# Main.net
KiCad netlist of a schematic drawn in Altium Designer
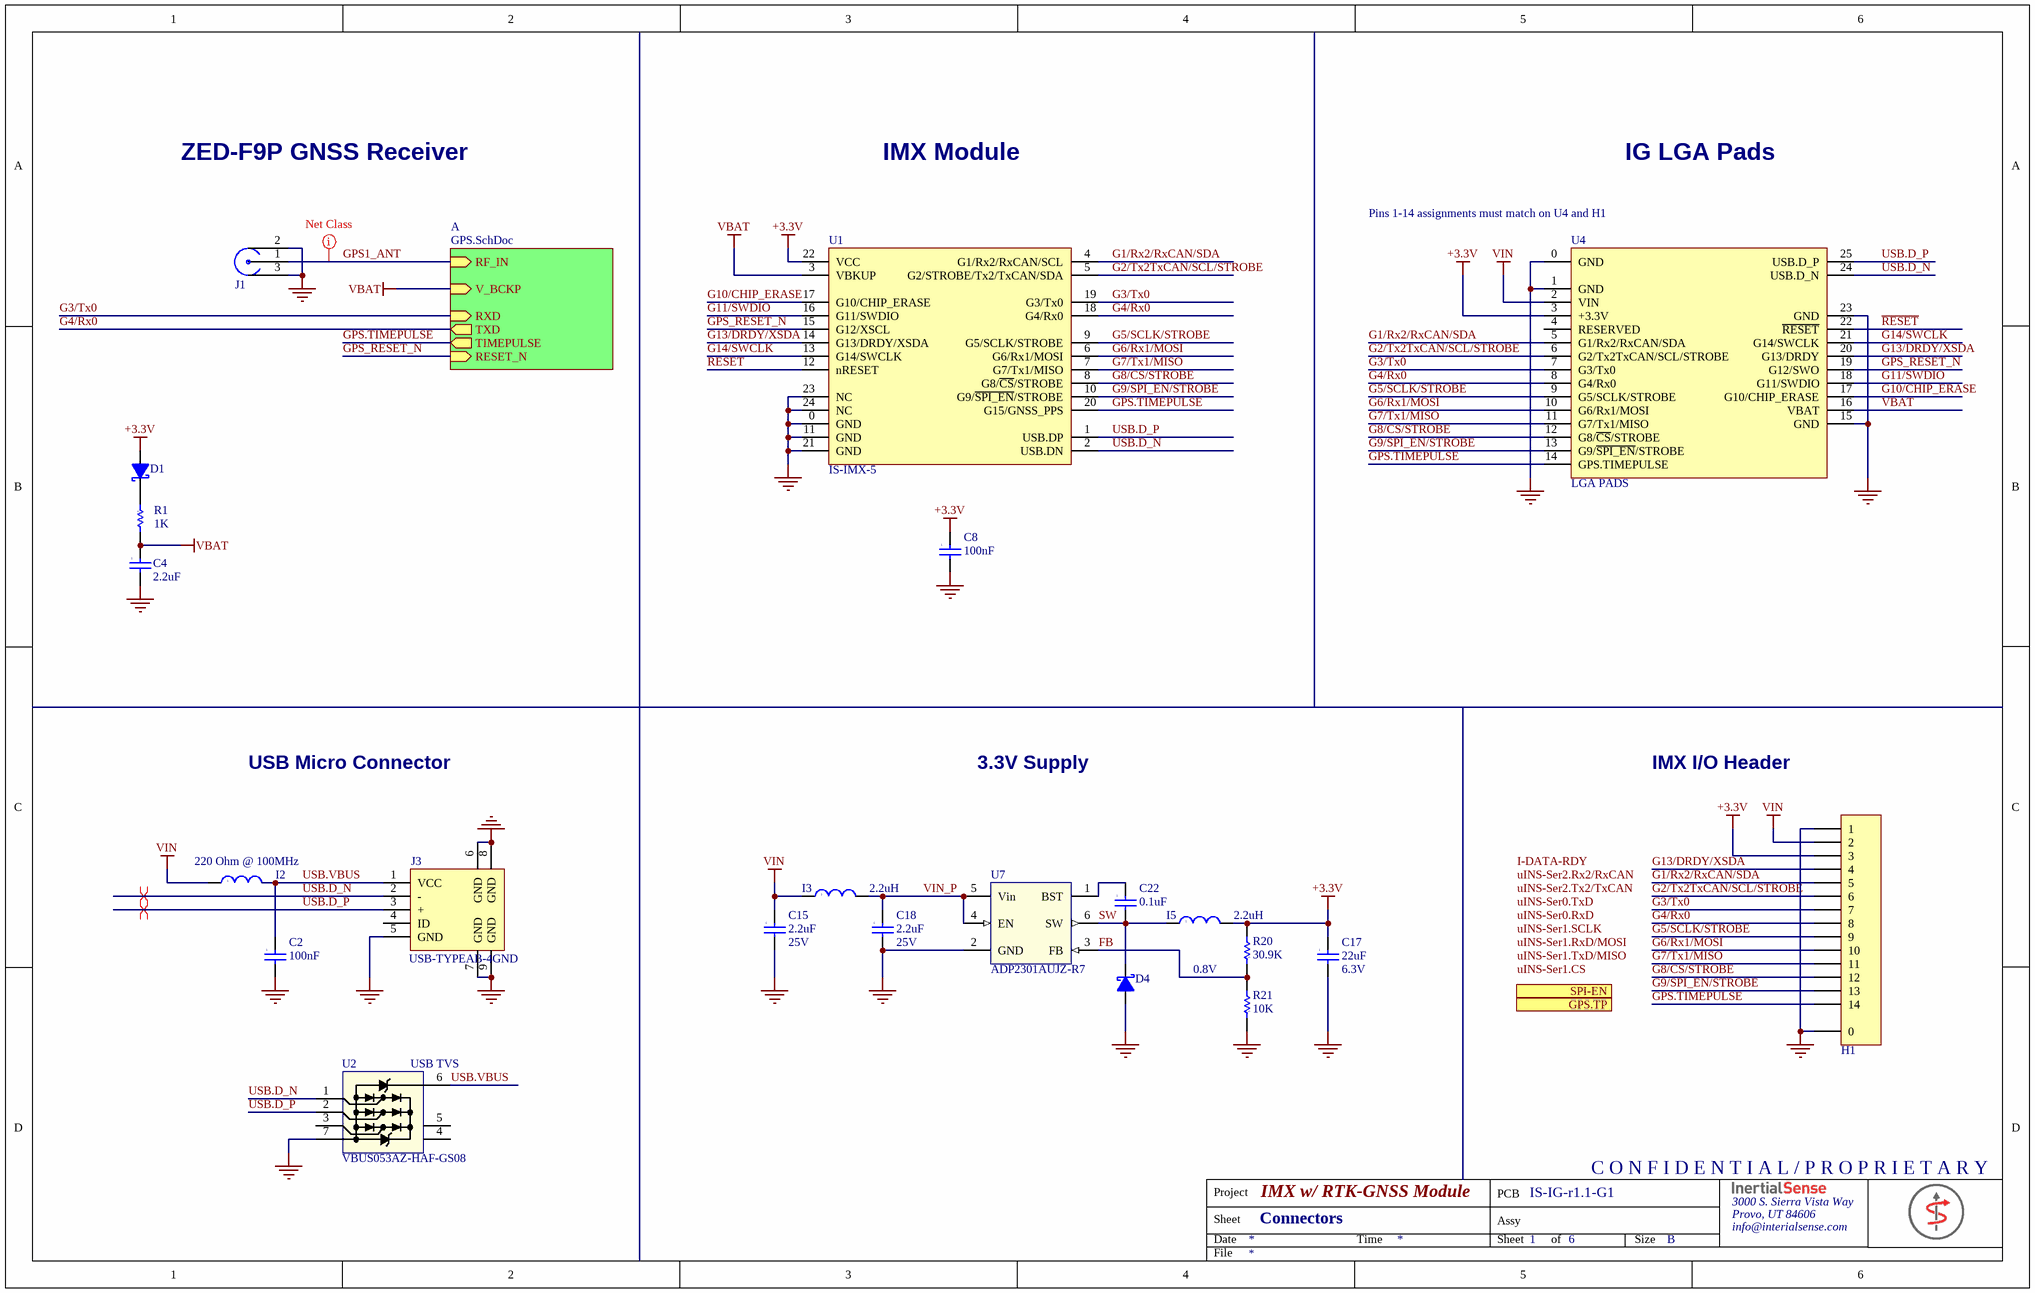
[diagram p0: Main.SchDoc]

(export (version "E")
  (design (tool "Eeschema 10.0.6"))
  (components
    (comp (ref "C2")
      (value "100nF")
      (footprint "0402")
      (description "CAP CER .10UF 50V X7R 10% 0402")
      (fields
        (field (name "MANUFACTURER") "TDK Corporation")
        (field (name "MANUFACTURER PART NUMBER") "C1005X7R1H104K")
        (field (name "PUBLISHER") "Altium Limited")
      )
      (libsource (lib "General") (part "Cap"))
    )
    (comp (ref "C4")
      (value "2.2uF")
      (footprint "0402")
      (description "0402 2.2 uF 6.3 V ±10% Tolerance X6S Multilayer Ceramic Capacitor")
      (fields
        (field (name "MANUFACTURER") "Murata")
        (field (name "MANUFACTURER PART NUMBER") "GRM155C80J225KE95D")
        (field (name "PUBLISHER") "Altium Limited")
      )
      (libsource (lib "") (part "Cap_1"))
    )
    (comp (ref "C8")
      (value "100nF")
      (footprint "0402")
      (description "CAP CER .10UF 50V X7R 10% 0402")
      (fields
        (field (name "MANUFACTURER") "TDK Corporation")
        (field (name "MANUFACTURER PART NUMBER") "C1005X7R1H104K")
        (field (name "PUBLISHER") "Altium Limited")
      )
      (libsource (lib "General") (part "Cap"))
    )
    (comp (ref "C15")
      (value "2.2uF")
      (footprint "0603")
      (description "CAP CER 2.2UF 25V X6S 0603")
      (fields
        (field (name "MANUFACTURER") "Murata")
        (field (name "MANUFACTURER PART NUMBER") "GRT188C81E225KE13D")
        (field (name "VOLTAGE RATING") "25V")
        (field (name "PUBLISHER") "Altium Limited")
      )
      (libsource (lib "") (part "Cap_1"))
    )
    (comp (ref "C17")
      (value "22uF")
      (footprint "0603")
      (description "CAP CER 22UF 6.3V X6S 0603")
      (fields
        (field (name "MANUFACTURER") "Murata")
        (field (name "MANUFACTURER PART NUMBER") "GRM188C80J226ME15D")
        (field (name "VOLTAGE RATING") "6.3V")
        (field (name "PUBLISHER") "Altium Limited")
      )
      (libsource (lib "") (part "Cap_1"))
    )
    (comp (ref "C18")
      (value "2.2uF")
      (footprint "0603")
      (description "CAP CER 2.2UF 25V X6S 0603")
      (fields
        (field (name "MANUFACTURER") "Murata")
        (field (name "MANUFACTURER PART NUMBER") "GRT188C81E225KE13D")
        (field (name "VOLTAGE RATING") "25V")
        (field (name "PUBLISHER") "Altium Limited")
      )
      (libsource (lib "") (part "Cap_1"))
    )
    (comp (ref "C22")
      (value "0.1uF")
      (footprint "0402")
      (description "CAP CER 0.1UF 50V X7R 0402")
      (fields
        (field (name "MANUFACTURER") "TDK")
        (field (name "MANUFACTURER PART NUMBER") "CGA2B3X7R1H104K050BB")
        (field (name "PUBLISHER") "Altium Limited")
      )
      (libsource (lib "") (part "Cap_1"))
    )
    (comp (ref "D1")
      (value "Diode - Schottky")
      (footprint "D0603B")
      (description "DIODE SCHOTTKY 30V 2A 0603")
      (fields
        (field (name "MANUFACTURER") "Vishay")
        (field (name "MANUFACTURER PART NUMBER") "VSKY20301608-G4-08")
      )
      (libsource (lib "General") (part "Diode - Schottky"))
    )
    (comp (ref "D4")
      (value "Diode - Schottky")
      (footprint "D0603B")
      (description "DIODE SCHOTTKY 30V 2A 0603")
      (fields
        (field (name "MANUFACTURER") "Vishay")
        (field (name "MANUFACTURER PART NUMBER") "VSKY20301608-G4-08")
      )
      (libsource (lib "General") (part "Diode - Schottky"))
    )
    (comp (ref "H1")
      (value "Hdr - 14pin - mount")
      (footprint "SM14B-GHS-TB(LF)(SN)")
      (description "Conn Shrouded Header HDR 14 POS 1.25mm Solder ST Top Entry SMD T/R")
      (fields
        (field (name "MANUFACTURER") "JST")
        (field (name "MANUFACTURER PART NUMBER") "SM14B-GHS-TB(LF)(SN)")
      )
      (libsource (lib "Connectors") (part "Hdr - 14pin - mount"))
    )
    (comp (ref "I2")
      (value "220 Ohm @ 100MHz")
      (footprint "I0603")
      (description "FERRITE CHIP 220 OHM 2500MA 0603")
      (fields
        (field (name "MANUFACTURER") "Murata Electronics North America")
        (field (name "MANUFACTURER PART NUMBER") "BLM18SG221TN1D")
      )
      (libsource (lib "") (part "Inductor_1"))
    )
    (comp (ref "I3")
      (value "2.2uH")
      (footprint "0806")
      (description "FIXED IND 2.2UH 1.2A 110 MOHM")
      (fields
        (field (name "MANUFACTURER") "TDK")
        (field (name "MANUFACTURER PART NUMBER") "MLP2016H2R2MT0S1")
      )
      (libsource (lib "General") (part "Inductor"))
    )
    (comp (ref "I5")
      (value "2.2uH")
      (footprint "0806")
      (description "FIXED IND 2.2UH 1.2A 110 MOHM")
      (fields
        (field (name "MANUFACTURER") "TDK")
        (field (name "MANUFACTURER PART NUMBER") "MLP2016H2R2MT0S1")
      )
      (libsource (lib "General") (part "Inductor"))
    )
    (comp (ref "J1")
      (value "RF - GND x 2")
      (footprint "RF UMC SMD")
      (description "CONN UMC RCPT STR 50 OHM SMD")
      (fields
        (field (name "MANUFACTURER") "Emerson Network Power Connectivity Johnson")
        (field (name "MANUFACTURER PART NUMBER") "128-0711-201")
      )
      (libsource (lib "Connectors") (part "RF - GND x 2"))
    )
    (comp (ref "J3")
      (value "USB-TYPEAB-4GND")
      (footprint "USB Micro AB R/A THR")
      (description "CONN USB AB 4POS")
      (fields
        (field (name "MANUFACTURER") "Amphenol FCI")
        (field (name "MANUFACTURER PART NUMBER") "10118194-0001LF")
      )
      (libsource (lib "Connectors") (part "USB-TYPEAB-4GND"))
    )
    (comp (ref "R1")
      (value "1K")
      (footprint "R0402")
      (description "1 kOhms ±1% 0.063W, 1/16W Chip Resistor 0402 (1005 Metric) Moisture Resistant Thick Film")
      (fields
        (field (name "MANUFACTURER") "Yageo")
        (field (name "MANUFACTURER PART NUMBER") "RC0402FR-071KL")
      )
      (libsource (lib "") (part "Res_1"))
    )
    (comp (ref "R20")
      (value "30.9K")
      (footprint "R0402")
      (description "RES TF 30.9K OHM 1% 1/16W 0402")
      (fields
        (field (name "MANUFACTURER") "Stackpole Electronics Inc")
        (field (name "MANUFACTURER PART NUMBER") "RMCF0402FT30K9")
      )
      (libsource (lib "General") (part "Res"))
    )
    (comp (ref "R21")
      (value "10K")
      (footprint "R0402")
      (description "RES 10.0K OHM 1/16W 1% 0402 SMD")
      (fields
        (field (name "MANUFACTURER") "Yageo")
        (field (name "MANUFACTURER PART NUMBER") "RC0402FR-0710KL")
      )
      (libsource (lib "General") (part "Res"))
    )
    (comp (ref "U1")
      (value "IMX")
      (footprint "IS-IMX-5.0")
      (description "Inertial Sense IMX")
      (fields
        (field (name "MANUFACTURER") "Inertial Sense")
        (field (name "MANUFACTURER PART NUMBER") "IS-IMX-5")
      )
      (libsource (lib "IS-IMX-5") (part "IS-IMX-5.0"))
    )
    (comp (ref "U2")
      (value "VBUS053")
      (footprint "QFN50P160X160X60-6N")
      (description "ESD SUPPRESS 5.5V 36W 3-Line USB")
      (fields
        (field (name "MANUFACTURER") "Vishay Semiconductors")
        (field (name "MANUFACTURER PART NUMBER") "VBUS053AZ-HAF-GS08")
      )
      (libsource (lib "ICs") (part "VBUS053"))
    )
    (comp (ref "U4")
      (value "LGA PADS")
      (footprint "IG-1.1-G1_LGA")
      (description "IMX multi-frequency RTK-GNSS Module")
      (libsource (lib "Sensors") (part "IG_1.1_LGA"))
    )
    (comp (ref "U7")
      (value "ADP2301")
      (footprint "MO-178-AB")
      (description "IC BUCK ADJ 1.2A 6TSOT")
      (fields
        (field (name "MANUFACTURER") "Analog Devices Inc")
        (field (name "MANUFACTURER PART NUMBER") "ADP2301AUJZ-R7")
      )
      (libsource (lib "ICs") (part "ADP2301"))
    )
  )
  (nets
    (net (code "1") (name "+3.3V") (class "Default")
      (node (ref "C17") (pin "1") (pinfunction "1_1") (pintype "passive"))
      (node (ref "C8") (pin "1") (pinfunction "1_1") (pintype "passive"))
      (node (ref "D1") (pin "A") (pinfunction "A_A") (pintype "passive"))
      (node (ref "H1") (pin "3") (pinfunction "3_3") (pintype "passive"))
      (node (ref "I5") (pin "2") (pinfunction "2_2") (pintype "passive"))
      (node (ref "R20") (pin "2") (pinfunction "2_2") (pintype "passive"))
      (node (ref "U1") (pin "22") (pinfunction "VCC_22") (pintype "power_in"))
      (node (ref "U4") (pin "3") (pinfunction "+3.3V_3") (pintype "passive"))
    )
    (net (code "2") (name "/FB") (class "Default")
      (node (ref "R20") (pin "1") (pinfunction "1_1") (pintype "passive"))
      (node (ref "R21") (pin "2") (pinfunction "2_2") (pintype "passive"))
      (node (ref "U7") (pin "3") (pinfunction "FB_3") (pintype "input"))
    )
    (net (code "3") (name "/G1{slash}Rx2{slash}RxCAN{slash}SDA") (class "Default")
      (node (ref "H1") (pin "5") (pinfunction "5_5") (pintype "passive"))
      (node (ref "U1") (pin "4") (pinfunction "G1/Rx2/RxCAN/SCL_4") (pintype "passive"))
      (node (ref "U4") (pin "5") (pinfunction "G1/Rx2/RxCAN/SDA_5") (pintype "passive"))
    )
    (net (code "4") (name "/G2{slash}Tx2TxCAN{slash}SCL{slash}STROBE") (class "Default")
      (node (ref "H1") (pin "6") (pinfunction "6_6") (pintype "passive"))
      (node (ref "U1") (pin "5") (pinfunction "G2/STROBE/Tx2/TxCAN/SDA_5") (pintype "passive"))
      (node (ref "U4") (pin "6") (pinfunction "G2/Tx2TxCAN/SCL/STROBE_6") (pintype "passive"))
    )
    (net (code "5") (name "/G3{slash}Tx0") (class "Default")
      (node (ref "H1") (pin "7") (pinfunction "7_7") (pintype "passive"))
      (node (ref "U1") (pin "19") (pinfunction "G3/Tx0_19") (pintype "passive"))
      (node (ref "U4") (pin "7") (pinfunction "G3/Tx0_7") (pintype "passive"))
    )
    (net (code "6") (name "/G4{slash}Rx0") (class "Default")
      (node (ref "H1") (pin "8") (pinfunction "8_8") (pintype "passive"))
      (node (ref "U1") (pin "18") (pinfunction "G4/Rx0_18") (pintype "passive"))
      (node (ref "U4") (pin "8") (pinfunction "G4/Rx0_8") (pintype "passive"))
    )
    (net (code "7") (name "/G5{slash}SCLK{slash}STROBE") (class "Default")
      (node (ref "H1") (pin "9") (pinfunction "9_9") (pintype "passive"))
      (node (ref "U1") (pin "9") (pinfunction "G5/SCLK/STROBE_9") (pintype "passive"))
      (node (ref "U4") (pin "9") (pinfunction "G5/SCLK/STROBE_9") (pintype "passive"))
    )
    (net (code "8") (name "/G6{slash}Rx1{slash}MOSI") (class "Default")
      (node (ref "H1") (pin "10") (pinfunction "10_10") (pintype "passive"))
      (node (ref "U1") (pin "6") (pinfunction "G6/Rx1/MOSI_6") (pintype "passive"))
      (node (ref "U4") (pin "10") (pinfunction "G6/Rx1/MOSI_10") (pintype "passive"))
    )
    (net (code "9") (name "/G7{slash}Tx1{slash}MISO") (class "Default")
      (node (ref "H1") (pin "11") (pinfunction "11_11") (pintype "passive"))
      (node (ref "U1") (pin "7") (pinfunction "G7/Tx1/MISO_7") (pintype "passive"))
      (node (ref "U4") (pin "11") (pinfunction "G7/Tx1/MISO_11") (pintype "passive"))
    )
    (net (code "10") (name "/G8{slash}~{CS}{slash}STROBE") (class "Default")
      (node (ref "H1") (pin "12") (pinfunction "12_12") (pintype "passive"))
      (node (ref "U1") (pin "8") (pinfunction "G8/~{CS}/STROBE_8") (pintype "passive"))
      (node (ref "U4") (pin "12") (pinfunction "G8/~{CS}/STROBE_12") (pintype "passive"))
    )
    (net (code "11") (name "/G9{slash}~{SPI_EN}{slash}STROBE") (class "Default")
      (node (ref "H1") (pin "13") (pinfunction "13_13") (pintype "passive"))
      (node (ref "U1") (pin "10") (pinfunction "G9/~{SPI_EN}/STROBE_10") (pintype "passive"))
      (node (ref "U4") (pin "13") (pinfunction "G9/~{SPI_EN}/STROBE_13") (pintype "passive"))
    )
    (net (code "12") (name "/G10{slash}CHIP_ERASE") (class "Default")
      (node (ref "U1") (pin "17") (pinfunction "G10/CHIP_ERASE_17") (pintype "passive"))
      (node (ref "U4") (pin "17") (pinfunction "G10/CHIP_ERASE_17") (pintype "passive"))
    )
    (net (code "13") (name "/G11{slash}SWDIO") (class "Default")
      (node (ref "U1") (pin "16") (pinfunction "G11/SWDIO_16") (pintype "passive"))
      (node (ref "U4") (pin "18") (pinfunction "G11/SWDIO_18") (pintype "passive"))
    )
    (net (code "14") (name "/G13{slash}DRDY{slash}XSDA") (class "Default")
      (node (ref "H1") (pin "4") (pinfunction "4_4") (pintype "passive"))
      (node (ref "U1") (pin "14") (pinfunction "G13/DRDY/XSDA_14") (pintype "passive"))
      (node (ref "U4") (pin "20") (pinfunction "G13/DRDY_20") (pintype "passive"))
    )
    (net (code "15") (name "/G14{slash}SWCLK") (class "Default")
      (node (ref "U1") (pin "13") (pinfunction "G14/SWCLK_13") (pintype "passive"))
      (node (ref "U4") (pin "21") (pinfunction "G14/SWCLK_21") (pintype "passive"))
    )
    (net (code "16") (name "/GPS.TIMEPULSE") (class "Default")
      (node (ref "H1") (pin "14") (pinfunction "14_14") (pintype "passive"))
      (node (ref "U1") (pin "20") (pinfunction "G15/GNSS_PPS_20") (pintype "passive"))
      (node (ref "U4") (pin "14") (pinfunction "GPS.TIMEPULSE_14") (pintype "passive"))
    )
    (net (code "18") (name "/GPS1_ANT") (class "Default")
      (node (ref "J1") (pin "1") (pinfunction "1_1") (pintype "passive"))
    )
    (net (code "19") (name "/GPS_RESET_N") (class "Default")
      (node (ref "U1") (pin "15") (pinfunction "G12/XSCL_15") (pintype "passive"))
      (node (ref "U4") (pin "19") (pinfunction "G12/SWO_19") (pintype "passive"))
    )
    (net (code "21") (name "/RESET") (class "Default")
      (node (ref "U1") (pin "12") (pinfunction "nRESET_12") (pintype "passive"))
      (node (ref "U4") (pin "22") (pinfunction "~{RESET}_22") (pintype "passive"))
    )
    (net (code "23") (name "/SW") (class "Default")
      (node (ref "C22") (pin "2") (pinfunction "2_2") (pintype "passive"))
      (node (ref "D4") (pin "C") (pinfunction "C_C") (pintype "passive"))
      (node (ref "I5") (pin "1") (pinfunction "1_1") (pintype "passive"))
      (node (ref "U7") (pin "6") (pinfunction "SW_6") (pintype "output"))
    )
    (net (code "24") (name "/USB.D_N") (class "Default")
      (node (ref "J3") (pin "2") (pinfunction "-_2") (pintype "passive"))
      (node (ref "U1") (pin "2") (pinfunction "USB.DN_2") (pintype "passive"))
      (node (ref "U2") (pin "1") (pintype "passive"))
      (node (ref "U4") (pin "24") (pinfunction "USB.D_N_24") (pintype "passive"))
    )
    (net (code "25") (name "/USB.D_P") (class "Default")
      (node (ref "J3") (pin "3") (pinfunction "+_3") (pintype "passive"))
      (node (ref "U1") (pin "1") (pinfunction "USB.DP_1") (pintype "passive"))
      (node (ref "U2") (pin "2") (pintype "passive"))
      (node (ref "U4") (pin "25") (pinfunction "USB.D_P_25") (pintype "passive"))
    )
    (net (code "26") (name "/USB.VBUS") (class "Default")
      (node (ref "C2") (pin "1") (pinfunction "1_1") (pintype "passive"))
      (node (ref "I2") (pin "2") (pinfunction "2_2") (pintype "passive"))
      (node (ref "J3") (pin "1") (pinfunction "VCC_1") (pintype "passive"))
      (node (ref "U2") (pin "6") (pintype "passive"))
    )
    (net (code "27") (name "/VIN_P") (class "Default")
      (node (ref "C18") (pin "1") (pinfunction "1_1") (pintype "passive"))
      (node (ref "I3") (pin "2") (pinfunction "2_2") (pintype "passive"))
      (node (ref "U7") (pin "4") (pinfunction "EN_4") (pintype "input"))
      (node (ref "U7") (pin "5") (pinfunction "Vin_5") (pintype "power_in"))
    )
    (net (code "36") (name "GND") (class "Default")
      (node (ref "C15") (pin "2") (pinfunction "2_2") (pintype "passive"))
      (node (ref "C17") (pin "2") (pinfunction "2_2") (pintype "passive"))
      (node (ref "C18") (pin "2") (pinfunction "2_2") (pintype "passive"))
      (node (ref "C2") (pin "2") (pinfunction "2_2") (pintype "passive"))
      (node (ref "C4") (pin "2") (pinfunction "2_2") (pintype "passive"))
      (node (ref "C8") (pin "2") (pinfunction "2_2") (pintype "passive"))
      (node (ref "D4") (pin "A") (pinfunction "A_A") (pintype "passive"))
      (node (ref "H1") (pin "0") (pinfunction "0_0") (pintype "passive"))
      (node (ref "H1") (pin "1") (pinfunction "1_1") (pintype "passive"))
      (node (ref "J1") (pin "2") (pinfunction "2_2") (pintype "passive"))
      (node (ref "J1") (pin "3") (pinfunction "3_3") (pintype "passive"))
      (node (ref "J3") (pin "5") (pinfunction "GND_5") (pintype "passive"))
      (node (ref "J3") (pin "6") (pinfunction "GND_6") (pintype "passive"))
      (node (ref "J3") (pin "7") (pinfunction "GND_7") (pintype "passive"))
      (node (ref "J3") (pin "8") (pinfunction "GND_8") (pintype "passive"))
      (node (ref "J3") (pin "9") (pinfunction "GND_9") (pintype "passive"))
      (node (ref "R21") (pin "1") (pinfunction "1_1") (pintype "passive"))
      (node (ref "U1") (pin "0") (pinfunction "GND_0") (pintype "power_in"))
      (node (ref "U1") (pin "11") (pinfunction "GND_11") (pintype "power_in"))
      (node (ref "U1") (pin "21") (pinfunction "GND_21") (pintype "power_in"))
      (node (ref "U1") (pin "23") (pinfunction "NC_23") (pintype "power_in"))
      (node (ref "U1") (pin "24") (pinfunction "NC_24") (pintype "power_in"))
      (node (ref "U2") (pin "7") (pintype "passive"))
      (node (ref "U4") (pin "0") (pinfunction "GND_0") (pintype "passive"))
      (node (ref "U4") (pin "1") (pinfunction "GND_1") (pintype "passive"))
      (node (ref "U4") (pin "15") (pinfunction "GND_15") (pintype "passive"))
      (node (ref "U4") (pin "23") (pinfunction "GND_23") (pintype "passive"))
      (node (ref "U7") (pin "2") (pinfunction "GND_2") (pintype "power_in"))
    )
    (net (code "37") (name "Net-(D1-PadC)") (class "Default")
      (node (ref "D1") (pin "C") (pinfunction "C_C") (pintype "passive"))
      (node (ref "R1") (pin "1") (pinfunction "1_1") (pintype "passive"))
    )
    (net (code "38") (name "Net-(U7-BST)") (class "Default")
      (node (ref "C22") (pin "1") (pinfunction "1_1") (pintype "passive"))
      (node (ref "U7") (pin "1") (pinfunction "BST_1") (pintype "passive"))
    )
    (net (code "39") (name "VBAT") (class "Default")
      (node (ref "C4") (pin "1") (pinfunction "1_1") (pintype "passive"))
      (node (ref "R1") (pin "2") (pinfunction "2_2") (pintype "passive"))
      (node (ref "U1") (pin "3") (pinfunction "VBKUP_3") (pintype "passive"))
      (node (ref "U4") (pin "16") (pinfunction "VBAT_16") (pintype "passive"))
    )
    (net (code "40") (name "VIN") (class "Default")
      (node (ref "C15") (pin "1") (pinfunction "1_1") (pintype "passive"))
      (node (ref "H1") (pin "2") (pinfunction "2_2") (pintype "passive"))
      (node (ref "I2") (pin "1") (pinfunction "1_1") (pintype "passive"))
      (node (ref "I3") (pin "1") (pinfunction "1_1") (pintype "passive"))
      (node (ref "U4") (pin "2") (pinfunction "VIN_2") (pintype "passive"))
    )
    (net (code "41") (name "unconnected-(J3-ID-Pad4)") (class "Default")
      (node (ref "J3") (pin "4") (pinfunction "ID_4") (pintype "passive"))
    )
    (net (code "42") (name "unconnected-(U2-Pad3)") (class "Default")
      (node (ref "U2") (pin "3") (pintype "passive"))
    )
    (net (code "43") (name "unconnected-(U2-nc-Pad4)") (class "Default")
      (node (ref "U2") (pin "4") (pinfunction "nc_4") (pintype "passive"))
    )
    (net (code "44") (name "unconnected-(U2-nc-Pad5)") (class "Default")
      (node (ref "U2") (pin "5") (pinfunction "nc_5") (pintype "passive"))
    )
    (net (code "45") (name "unconnected-(U4-RESERVED-Pad4)") (class "Default")
      (node (ref "U4") (pin "4") (pinfunction "RESERVED_4") (pintype "passive"))
    )
  )
)
